# rev02_2.net
KiCad netlist of a schematic drawn in Altium Designer
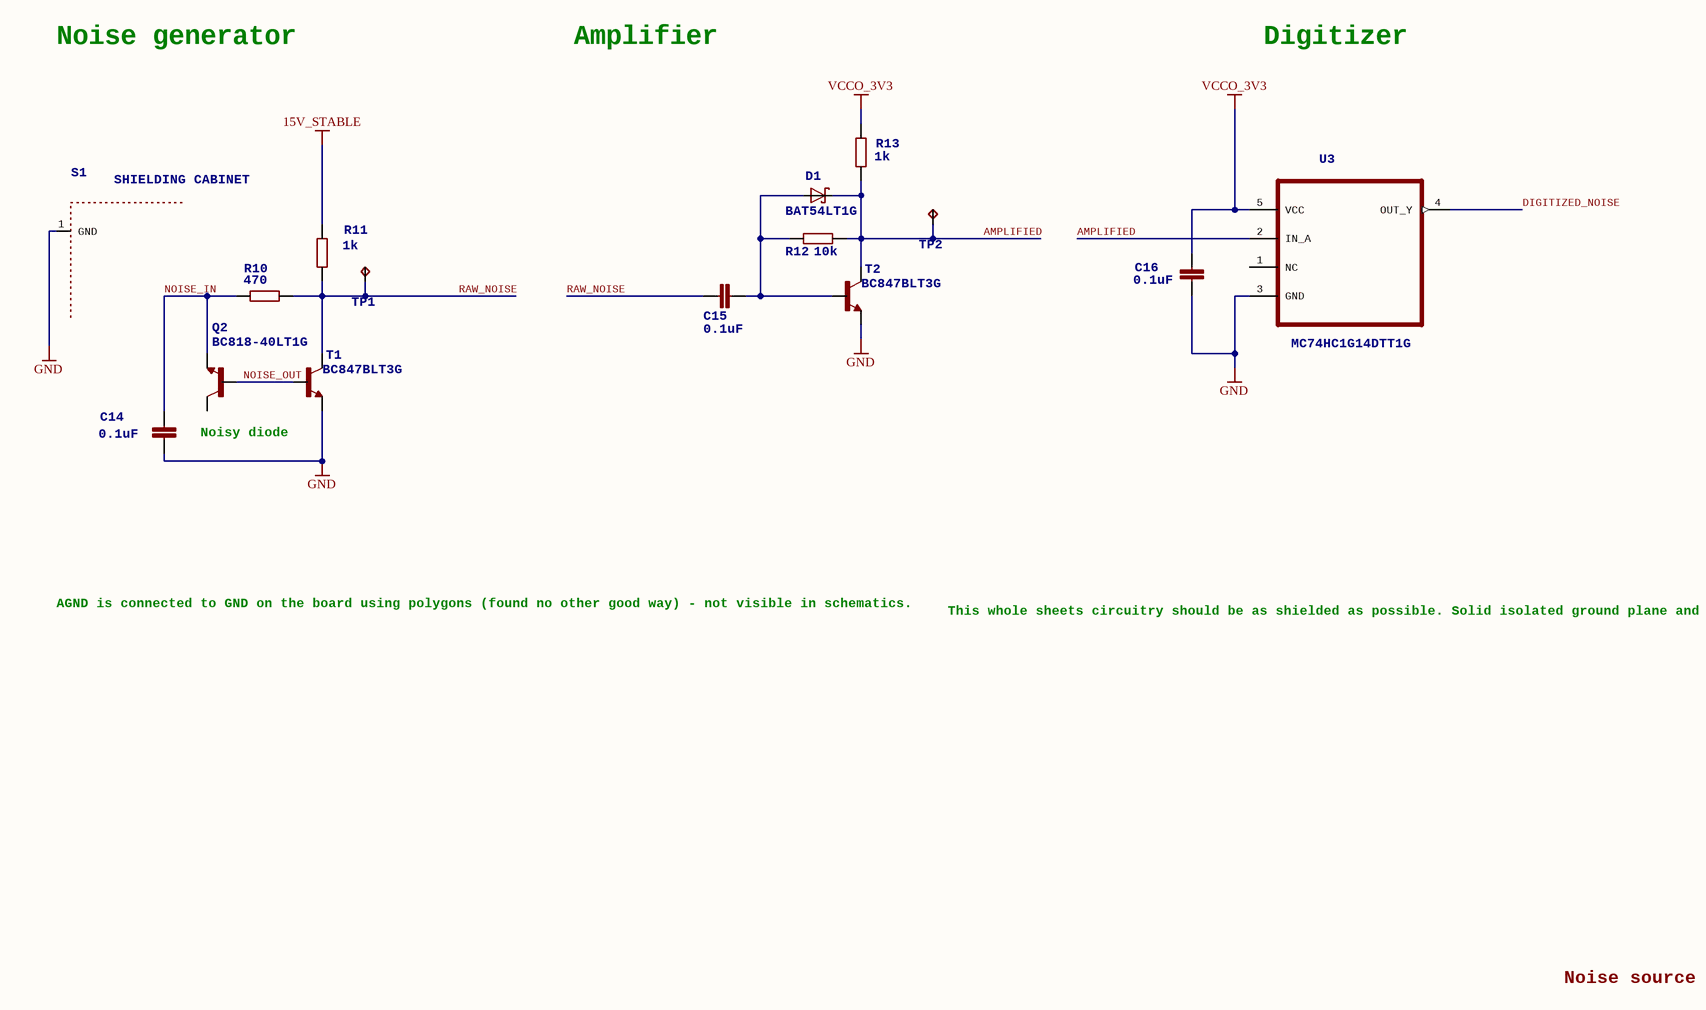
[diagram p0: rev02_2.SchDoc]

(export (version "E")
  (design (tool "Eeschema 10.0.6"))
  (components
    (comp (ref "C14")
      (value "0.1uF")
      (footprint "C_0402")
      (description "0402 CAPACITOR")
      (libsource (lib "") (part "C-EUC0603_1"))
    )
    (comp (ref "C15")
      (value "0.1uF")
      (footprint "C_0402")
      (description "0402 CAPACITOR")
      (libsource (lib "resistor") (part "C-EUC0603"))
    )
    (comp (ref "C16")
      (value "0.1uF")
      (footprint "C_0402")
      (description "0402 CAPACITOR")
      (libsource (lib "") (part "C-EUC0603_1"))
    )
    (comp (ref "D1")
      (value "BAT54LT1G")
      (footprint "SOT-23")
      (description "OnSemi Schottky Diode")
      (libsource (lib "diode") (part "BAT54"))
    )
    (comp (ref "Q2")
      (value "BC818-40LT1G")
      (footprint "SOT-23")
      (description "NPN Transistor")
      (libsource (lib "") (part "BC818*SMD_1"))
    )
    (comp (ref "R10")
      (value "470")
      (footprint "R_0402")
      (description "0402 Resistor 1%")
      (libsource (lib "resistor") (part "R-EU_R0402"))
    )
    (comp (ref "R11")
      (value "1k")
      (footprint "R_0402")
      (description "0402 Resistor 1%")
      (libsource (lib "resistor") (part "R-EU_R0402"))
    )
    (comp (ref "R12")
      (value "10k")
      (footprint "R_0402")
      (description "0402 Resistor 1%")
      (libsource (lib "resistor") (part "R-EU_R0402"))
    )
    (comp (ref "R13")
      (value "1k")
      (footprint "R_0402")
      (description "0402 Resistor 1%")
      (libsource (lib "resistor") (part "R-EU_R0402"))
    )
    (comp (ref "S1")
      (value "SHIELDING CABINET")
      (footprint "WE-SHC_36103205_NO_CREAM")
      (description "WE-SHC Shielding cabinet")
      (libsource (lib "rev02_1") (part "WE-SHC"))
    )
    (comp (ref "T1")
      (value "BC847BLT3G")
      (footprint "SOT-23")
      (description "NPN Transistor")
      (libsource (lib "rev02_1") (part "BC818*SMD"))
    )
    (comp (ref "T2")
      (value "BC847BLT3G")
      (footprint "SOT-23")
      (description "NPN Transistor")
      (libsource (lib "rev02_1") (part "BC818*SMD"))
    )
    (comp (ref "TP1")
      (value "TPB1,27")
      (footprint "B1,27")
      (description "Test pad")
      (libsource (lib "rev02_1") (part "TPB1,27"))
    )
    (comp (ref "TP2")
      (value "TPB1,27")
      (footprint "B1,27")
      (description "Test pad")
      (libsource (lib "rev02_1") (part "TPB1,27"))
    )
    (comp (ref "U3")
      (value "MC74HC1G14DTT1G")
      (footprint "SOT-23-5")
      (description "Single Inverter with Schmitt-Trigger Input")
      (fields (field (name ">NAME") "U3") (field (name ">VALUE") "MC74HC1G14DTT1G"))
      (libsource (lib "MC74HC1G14DTT1G") (part "MC74HC1G14DTT1G"))
    )
  )
  (nets
    (net (code "1") (name "/AMPLIFIED") (class "Default")
      (node (ref "D1") (pin "3") (pinfunction "C_3") (pintype "passive"))
      (node (ref "R12") (pin "2") (pinfunction "2_2") (pintype "passive"))
      (node (ref "R13") (pin "1") (pinfunction "1_1") (pintype "passive"))
      (node (ref "T2") (pin "3") (pinfunction "C_3") (pintype "passive"))
      (node (ref "TP2") (pin "TP") (pinfunction "TP_TP") (pintype "passive"))
      (node (ref "U3") (pin "2") (pinfunction "IN_A_2") (pintype "passive"))
    )
    (net (code "2") (name "/DIGITIZED_NOISE") (class "Default")
      (node (ref "U3") (pin "4") (pinfunction "OUT_Y_4") (pintype "output"))
    )
    (net (code "3") (name "/NOISE_IN") (class "Default")
      (node (ref "C14") (pin "2") (pinfunction "2_2") (pintype "passive"))
      (node (ref "Q2") (pin "2") (pinfunction "E_2") (pintype "passive"))
      (node (ref "R10") (pin "2") (pinfunction "2_2") (pintype "passive"))
    )
    (net (code "4") (name "/NOISE_OUT") (class "Default")
      (node (ref "Q2") (pin "1") (pinfunction "B_1") (pintype "passive"))
      (node (ref "T1") (pin "1") (pinfunction "B_1") (pintype "passive"))
    )
    (net (code "5") (name "/RAW_NOISE") (class "Default")
      (node (ref "C15") (pin "1") (pinfunction "1_1") (pintype "passive"))
      (node (ref "R10") (pin "1") (pinfunction "1_1") (pintype "passive"))
      (node (ref "R11") (pin "2") (pinfunction "2_2") (pintype "passive"))
      (node (ref "T1") (pin "3") (pinfunction "C_3") (pintype "passive"))
      (node (ref "TP1") (pin "TP") (pinfunction "TP_TP") (pintype "passive"))
    )
    (net (code "6") (name "15V_STABLE") (class "Default")
      (node (ref "R11") (pin "1") (pinfunction "1_1") (pintype "passive"))
    )
    (net (code "7") (name "GND") (class "Default")
      (node (ref "C14") (pin "1") (pinfunction "1_1") (pintype "passive"))
      (node (ref "C16") (pin "1") (pinfunction "1_1") (pintype "passive"))
      (node (ref "S1") (pin "1") (pinfunction "GND_1") (pintype "power_in"))
      (node (ref "T1") (pin "2") (pinfunction "E_2") (pintype "passive"))
      (node (ref "T2") (pin "2") (pinfunction "E_2") (pintype "passive"))
      (node (ref "U3") (pin "3") (pinfunction "GND_3") (pintype "passive"))
    )
    (net (code "8") (name "Net-(D1-A)") (class "Default")
      (node (ref "C15") (pin "2") (pinfunction "2_2") (pintype "passive"))
      (node (ref "D1") (pin "1") (pinfunction "A_1") (pintype "passive"))
      (node (ref "R12") (pin "1") (pinfunction "1_1") (pintype "passive"))
      (node (ref "T2") (pin "1") (pinfunction "B_1") (pintype "passive"))
    )
    (net (code "9") (name "VCCO_3V3") (class "Default")
      (node (ref "C16") (pin "2") (pinfunction "2_2") (pintype "passive"))
      (node (ref "R13") (pin "2") (pinfunction "2_2") (pintype "passive"))
      (node (ref "U3") (pin "5") (pinfunction "VCC_5") (pintype "power_in"))
    )
    (net (code "10") (name "unconnected-(Q2-C-Pad3)") (class "Default")
      (node (ref "Q2") (pin "3") (pinfunction "C_3") (pintype "passive"))
    )
    (net (code "11") (name "unconnected-(U3-NC-Pad1)") (class "Default")
      (node (ref "U3") (pin "1") (pinfunction "NC_1") (pintype "passive"))
    )
  )
)
